# ESP8862.net
KiCad netlist of a schematic drawn in Altium Designer
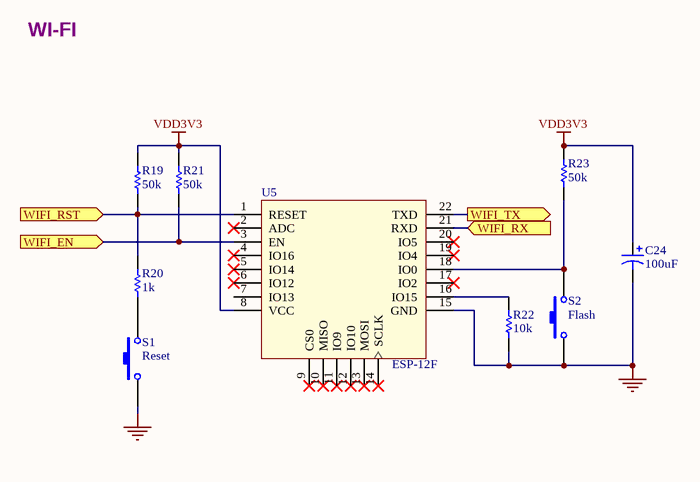
[diagram p0: ESP8862.SchDoc]

(export (version "E")
  (design (tool "Eeschema 10.0.6"))
  (components
    (comp (ref "C24")
      (value "100uF")
      (footprint "AVX-B_TANTALUM-SMD-100UF-6.3V(AVX-B)(Primary)")
      (description "Polarized Capacitor (Axial)")
      (libsource (lib "POP_lib") (part "Cap Pol2"))
    )
    (comp (ref "R19")
      (value "50k")
      (footprint "RESC1608X55N")
      (description "Resistor")
      (libsource (lib "POP_lib") (part "Resistor"))
    )
    (comp (ref "R20")
      (value "1k")
      (footprint "RESC1608X55N")
      (description "Resistor")
      (libsource (lib "POP_lib") (part "Resistor"))
    )
    (comp (ref "R21")
      (value "50k")
      (footprint "RESC1608X55N")
      (description "Resistor")
      (libsource (lib "POP_lib") (part "Resistor"))
    )
    (comp (ref "R22")
      (value "10k")
      (footprint "RESC1608X55N")
      (description "Resistor")
      (fields (field (name "PUBLISHER") "Altium Limited"))
      (libsource (lib "POP_lib") (part "Resistor"))
    )
    (comp (ref "R23")
      (value "50k")
      (footprint "RESC1608X55N")
      (description "Resistor")
      (libsource (lib "POP_lib") (part "Resistor"))
    )
    (comp (ref "S1")
      (value "Reset")
      (footprint "SWITCH_4x6")
      (description "Switch")
      (libsource (lib "POP_lib") (part "SW-PB"))
    )
    (comp (ref "S2")
      (value "Flash")
      (footprint "SWITCH_4x6")
      (description "Switch")
      (libsource (lib "POP_lib") (part "SW-PB"))
    )
    (comp (ref "U5") (value "ESP-12F") (footprint "ESP_12_E") (libsource (lib "POP_lib") (part "ESP-12F")))
  )
  (nets
    (net (code "1") (name "/WIFI_EN") (class "Default")
      (node (ref "R21") (pin "1") (pinfunction "1_1") (pintype "passive"))
      (node (ref "U5") (pin "3") (pinfunction "EN_3") (pintype "passive"))
    )
    (net (code "2") (name "/WIFI_RST") (class "Default")
      (node (ref "R19") (pin "1") (pinfunction "1_1") (pintype "passive"))
      (node (ref "R20") (pin "2") (pinfunction "2_2") (pintype "passive"))
      (node (ref "U5") (pin "1") (pinfunction "RESET_1") (pintype "passive"))
    )
    (net (code "3") (name "/WIFI_RX") (class "Default")
      (node (ref "U5") (pin "21") (pinfunction "RXD_21") (pintype "passive"))
    )
    (net (code "4") (name "/WIFI_TX") (class "Default")
      (node (ref "U5") (pin "22") (pinfunction "TXD_22") (pintype "passive"))
    )
    (net (code "5") (name "GND") (class "Default")
      (node (ref "C24") (pin "2") (pinfunction "2_2") (pintype "passive"))
      (node (ref "R22") (pin "1") (pinfunction "1_1") (pintype "passive"))
      (node (ref "S1") (pin "1") (pinfunction "1_1") (pintype "passive"))
      (node (ref "S2") (pin "1") (pinfunction "1_1") (pintype "passive"))
      (node (ref "U5") (pin "15") (pinfunction "GND_15") (pintype "passive"))
    )
    (net (code "6") (name "Net-(R20-Pad1)") (class "Default")
      (node (ref "R20") (pin "1") (pinfunction "1_1") (pintype "passive"))
      (node (ref "S1") (pin "2") (pinfunction "2_2") (pintype "passive"))
    )
    (net (code "7") (name "Net-(U5-IO0)") (class "Default")
      (node (ref "R23") (pin "1") (pinfunction "1_1") (pintype "passive"))
      (node (ref "S2") (pin "2") (pinfunction "2_2") (pintype "passive"))
      (node (ref "U5") (pin "18") (pinfunction "IO0_18") (pintype "passive"))
    )
    (net (code "8") (name "Net-(U5-IO15)") (class "Default")
      (node (ref "R22") (pin "2") (pinfunction "2_2") (pintype "passive"))
      (node (ref "U5") (pin "16") (pinfunction "IO15_16") (pintype "passive"))
    )
    (net (code "9") (name "VDD3V3") (class "Default")
      (node (ref "C24") (pin "1") (pinfunction "1_1") (pintype "passive"))
      (node (ref "R19") (pin "2") (pinfunction "2_2") (pintype "passive"))
      (node (ref "R21") (pin "2") (pinfunction "2_2") (pintype "passive"))
      (node (ref "R23") (pin "2") (pinfunction "2_2") (pintype "passive"))
      (node (ref "U5") (pin "8") (pinfunction "VCC_8") (pintype "passive"))
    )
    (net (code "10") (name "unconnected-(U5-ADC-Pad2)") (class "Default")
      (node (ref "U5") (pin "2") (pinfunction "ADC_2") (pintype "passive+no_connect"))
    )
    (net (code "11") (name "unconnected-(U5-CS0-Pad9)") (class "Default")
      (node (ref "U5") (pin "9") (pinfunction "CS0_9") (pintype "passive+no_connect"))
    )
    (net (code "12") (name "unconnected-(U5-IO2-Pad17)") (class "Default")
      (node (ref "U5") (pin "17") (pinfunction "IO2_17") (pintype "passive+no_connect"))
    )
    (net (code "13") (name "unconnected-(U5-IO4-Pad19)") (class "Default")
      (node (ref "U5") (pin "19") (pinfunction "IO4_19") (pintype "passive+no_connect"))
    )
    (net (code "14") (name "unconnected-(U5-IO5-Pad20)") (class "Default")
      (node (ref "U5") (pin "20") (pinfunction "IO5_20") (pintype "passive+no_connect"))
    )
    (net (code "15") (name "unconnected-(U5-IO9-Pad11)") (class "Default")
      (node (ref "U5") (pin "11") (pinfunction "IO9_11") (pintype "passive+no_connect"))
    )
    (net (code "16") (name "unconnected-(U5-IO10-Pad12)") (class "Default")
      (node (ref "U5") (pin "12") (pinfunction "IO10_12") (pintype "passive+no_connect"))
    )
    (net (code "17") (name "unconnected-(U5-IO12-Pad6)") (class "Default")
      (node (ref "U5") (pin "6") (pinfunction "IO12_6") (pintype "passive+no_connect"))
    )
    (net (code "18") (name "unconnected-(U5-IO13-Pad7)") (class "Default")
      (node (ref "U5") (pin "7") (pinfunction "IO13_7") (pintype "passive"))
    )
    (net (code "19") (name "unconnected-(U5-IO14-Pad5)") (class "Default")
      (node (ref "U5") (pin "5") (pinfunction "IO14_5") (pintype "passive+no_connect"))
    )
    (net (code "20") (name "unconnected-(U5-IO16-Pad4)") (class "Default")
      (node (ref "U5") (pin "4") (pinfunction "IO16_4") (pintype "passive+no_connect"))
    )
    (net (code "21") (name "unconnected-(U5-MISO-Pad10)") (class "Default")
      (node (ref "U5") (pin "10") (pinfunction "MISO_10") (pintype "passive+no_connect"))
    )
    (net (code "22") (name "unconnected-(U5-MOSI-Pad13)") (class "Default")
      (node (ref "U5") (pin "13") (pinfunction "MOSI_13") (pintype "passive+no_connect"))
    )
    (net (code "23") (name "unconnected-(U5-SCLK-Pad14)") (class "Default")
      (node (ref "U5") (pin "14") (pinfunction "SCLK_14") (pintype "passive+no_connect"))
    )
  )
)
